# bridgestuff.net
KiCad netlist of a schematic drawn in EAGLE
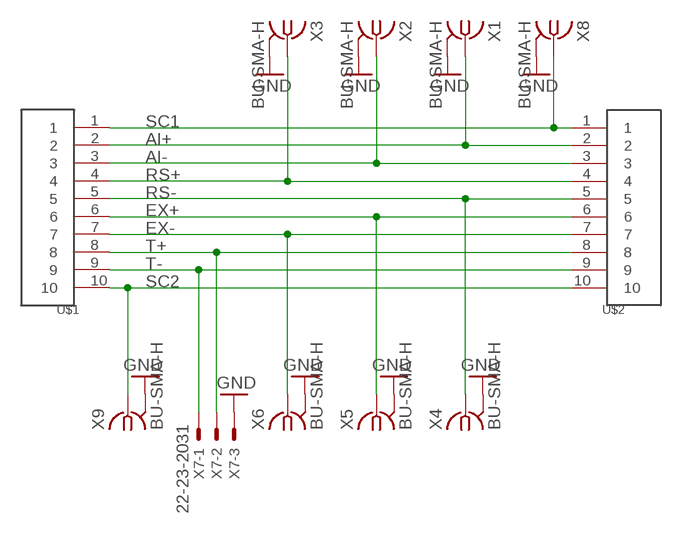
[diagram p0: schematic, sheet 1]

(export (version "E")
  (design (tool "Eeschema 10.0.6"))
  (components
    (comp (ref "U$1")
      (value "RJ50-STEWARD")
      (footprint "eagle-import:RJ50")
      (libsource (lib "eagle-import") (part "RJ50-STEWARD"))
    )
    (comp (ref "U$2")
      (value "RJ50-STEWARD")
      (footprint "eagle-import:RJ50")
      (libsource (lib "eagle-import") (part "RJ50-STEWARD"))
    )
    (comp (ref "X1")
      (value "BU-SMA-H")
      (footprint "eagle-import:BU-SMA-H")
      (libsource (lib "eagle-import") (part "BU-SMA-H"))
    )
    (comp (ref "X2")
      (value "BU-SMA-H")
      (footprint "eagle-import:BU-SMA-H")
      (libsource (lib "eagle-import") (part "BU-SMA-H"))
    )
    (comp (ref "X3")
      (value "BU-SMA-H")
      (footprint "eagle-import:BU-SMA-H")
      (libsource (lib "eagle-import") (part "BU-SMA-H"))
    )
    (comp (ref "X4")
      (value "BU-SMA-H")
      (footprint "eagle-import:BU-SMA-H")
      (libsource (lib "eagle-import") (part "BU-SMA-H"))
    )
    (comp (ref "X5")
      (value "BU-SMA-H")
      (footprint "eagle-import:BU-SMA-H")
      (libsource (lib "eagle-import") (part "BU-SMA-H"))
    )
    (comp (ref "X6")
      (value "BU-SMA-H")
      (footprint "eagle-import:BU-SMA-H")
      (libsource (lib "eagle-import") (part "BU-SMA-H"))
    )
    (comp (ref "X7")
      (value "22-23-2031")
      (footprint "eagle-import:22-23-2031")
      (fields (field (name "MF") "MOLEX"))
      (libsource (lib "eagle-import") (part "22-23-2031"))
    )
    (comp (ref "X8")
      (value "BU-SMA-H")
      (footprint "eagle-import:BU-SMA-H")
      (libsource (lib "eagle-import") (part "BU-SMA-H"))
    )
    (comp (ref "X9")
      (value "BU-SMA-H")
      (footprint "eagle-import:BU-SMA-H")
      (libsource (lib "eagle-import") (part "BU-SMA-H"))
    )
  )
  (nets
    (net (code "1") (name "/AI+") (class "Default")
      (node (ref "U$1") (pin "2") (pinfunction "2_2") (pintype "bidirectional"))
      (node (ref "U$2") (pin "2") (pinfunction "2_2") (pintype "bidirectional"))
      (node (ref "X1") (pin "1") (pinfunction "1_1") (pintype "passive"))
    )
    (net (code "2") (name "/AI-") (class "Default")
      (node (ref "U$1") (pin "3") (pinfunction "3_3") (pintype "bidirectional"))
      (node (ref "U$2") (pin "3") (pinfunction "3_3") (pintype "bidirectional"))
      (node (ref "X2") (pin "1") (pinfunction "1_1") (pintype "passive"))
    )
    (net (code "3") (name "/EX+") (class "Default")
      (node (ref "U$1") (pin "6") (pinfunction "6_6") (pintype "bidirectional"))
      (node (ref "U$2") (pin "6") (pinfunction "6_6") (pintype "bidirectional"))
      (node (ref "X5") (pin "1") (pinfunction "1_1") (pintype "passive"))
    )
    (net (code "4") (name "/EX-") (class "Default")
      (node (ref "U$1") (pin "7") (pinfunction "7_7") (pintype "bidirectional"))
      (node (ref "U$2") (pin "7") (pinfunction "7_7") (pintype "bidirectional"))
      (node (ref "X6") (pin "1") (pinfunction "1_1") (pintype "passive"))
    )
    (net (code "5") (name "/RS+") (class "Default")
      (node (ref "U$1") (pin "4") (pinfunction "4_4") (pintype "bidirectional"))
      (node (ref "U$2") (pin "4") (pinfunction "4_4") (pintype "bidirectional"))
      (node (ref "X3") (pin "1") (pinfunction "1_1") (pintype "passive"))
    )
    (net (code "6") (name "/RS-") (class "Default")
      (node (ref "U$1") (pin "5") (pinfunction "5_5") (pintype "bidirectional"))
      (node (ref "U$2") (pin "5") (pinfunction "5_5") (pintype "bidirectional"))
      (node (ref "X4") (pin "1") (pinfunction "1_1") (pintype "passive"))
    )
    (net (code "7") (name "/SC1") (class "Default")
      (node (ref "U$1") (pin "1") (pinfunction "1_1") (pintype "bidirectional"))
      (node (ref "U$2") (pin "1") (pinfunction "1_1") (pintype "bidirectional"))
      (node (ref "X8") (pin "1") (pinfunction "1_1") (pintype "passive"))
    )
    (net (code "8") (name "/SC2") (class "Default")
      (node (ref "U$1") (pin "10") (pinfunction "10_10") (pintype "bidirectional"))
      (node (ref "U$2") (pin "10") (pinfunction "10_10") (pintype "bidirectional"))
      (node (ref "X9") (pin "1") (pinfunction "1_1") (pintype "passive"))
    )
    (net (code "9") (name "/T+") (class "Default")
      (node (ref "U$1") (pin "8") (pinfunction "8_8") (pintype "bidirectional"))
      (node (ref "U$2") (pin "8") (pinfunction "8_8") (pintype "bidirectional"))
      (node (ref "X7") (pin "2") (pinfunction "S_2") (pintype "passive"))
    )
    (net (code "10") (name "/T-") (class "Default")
      (node (ref "U$1") (pin "9") (pinfunction "9_9") (pintype "bidirectional"))
      (node (ref "U$2") (pin "9") (pinfunction "9_9") (pintype "bidirectional"))
      (node (ref "X7") (pin "1") (pinfunction "S_1") (pintype "passive"))
    )
    (net (code "11") (name "GND") (class "Default")
      (node (ref "X1") (pin "2") (pinfunction "2_2") (pintype "passive"))
      (node (ref "X1") (pin "3") (pinfunction "2_3") (pintype "passive"))
      (node (ref "X1") (pin "4") (pinfunction "2_4") (pintype "passive"))
      (node (ref "X1") (pin "5") (pinfunction "2_5") (pintype "passive"))
      (node (ref "X2") (pin "2") (pinfunction "2_2") (pintype "passive"))
      (node (ref "X2") (pin "3") (pinfunction "2_3") (pintype "passive"))
      (node (ref "X2") (pin "4") (pinfunction "2_4") (pintype "passive"))
      (node (ref "X2") (pin "5") (pinfunction "2_5") (pintype "passive"))
      (node (ref "X3") (pin "2") (pinfunction "2_2") (pintype "passive"))
      (node (ref "X3") (pin "3") (pinfunction "2_3") (pintype "passive"))
      (node (ref "X3") (pin "4") (pinfunction "2_4") (pintype "passive"))
      (node (ref "X3") (pin "5") (pinfunction "2_5") (pintype "passive"))
      (node (ref "X4") (pin "2") (pinfunction "2_2") (pintype "passive"))
      (node (ref "X4") (pin "3") (pinfunction "2_3") (pintype "passive"))
      (node (ref "X4") (pin "4") (pinfunction "2_4") (pintype "passive"))
      (node (ref "X4") (pin "5") (pinfunction "2_5") (pintype "passive"))
      (node (ref "X5") (pin "2") (pinfunction "2_2") (pintype "passive"))
      (node (ref "X5") (pin "3") (pinfunction "2_3") (pintype "passive"))
      (node (ref "X5") (pin "4") (pinfunction "2_4") (pintype "passive"))
      (node (ref "X5") (pin "5") (pinfunction "2_5") (pintype "passive"))
      (node (ref "X6") (pin "2") (pinfunction "2_2") (pintype "passive"))
      (node (ref "X6") (pin "3") (pinfunction "2_3") (pintype "passive"))
      (node (ref "X6") (pin "4") (pinfunction "2_4") (pintype "passive"))
      (node (ref "X6") (pin "5") (pinfunction "2_5") (pintype "passive"))
      (node (ref "X7") (pin "3") (pinfunction "S_3") (pintype "passive"))
      (node (ref "X8") (pin "2") (pinfunction "2_2") (pintype "passive"))
      (node (ref "X8") (pin "3") (pinfunction "2_3") (pintype "passive"))
      (node (ref "X8") (pin "4") (pinfunction "2_4") (pintype "passive"))
      (node (ref "X8") (pin "5") (pinfunction "2_5") (pintype "passive"))
      (node (ref "X9") (pin "2") (pinfunction "2_2") (pintype "passive"))
      (node (ref "X9") (pin "3") (pinfunction "2_3") (pintype "passive"))
      (node (ref "X9") (pin "4") (pinfunction "2_4") (pintype "passive"))
      (node (ref "X9") (pin "5") (pinfunction "2_5") (pintype "passive"))
    )
  )
)
